# motherboard.net
KiCad netlist of a schematic drawn in EasyEDA Pro
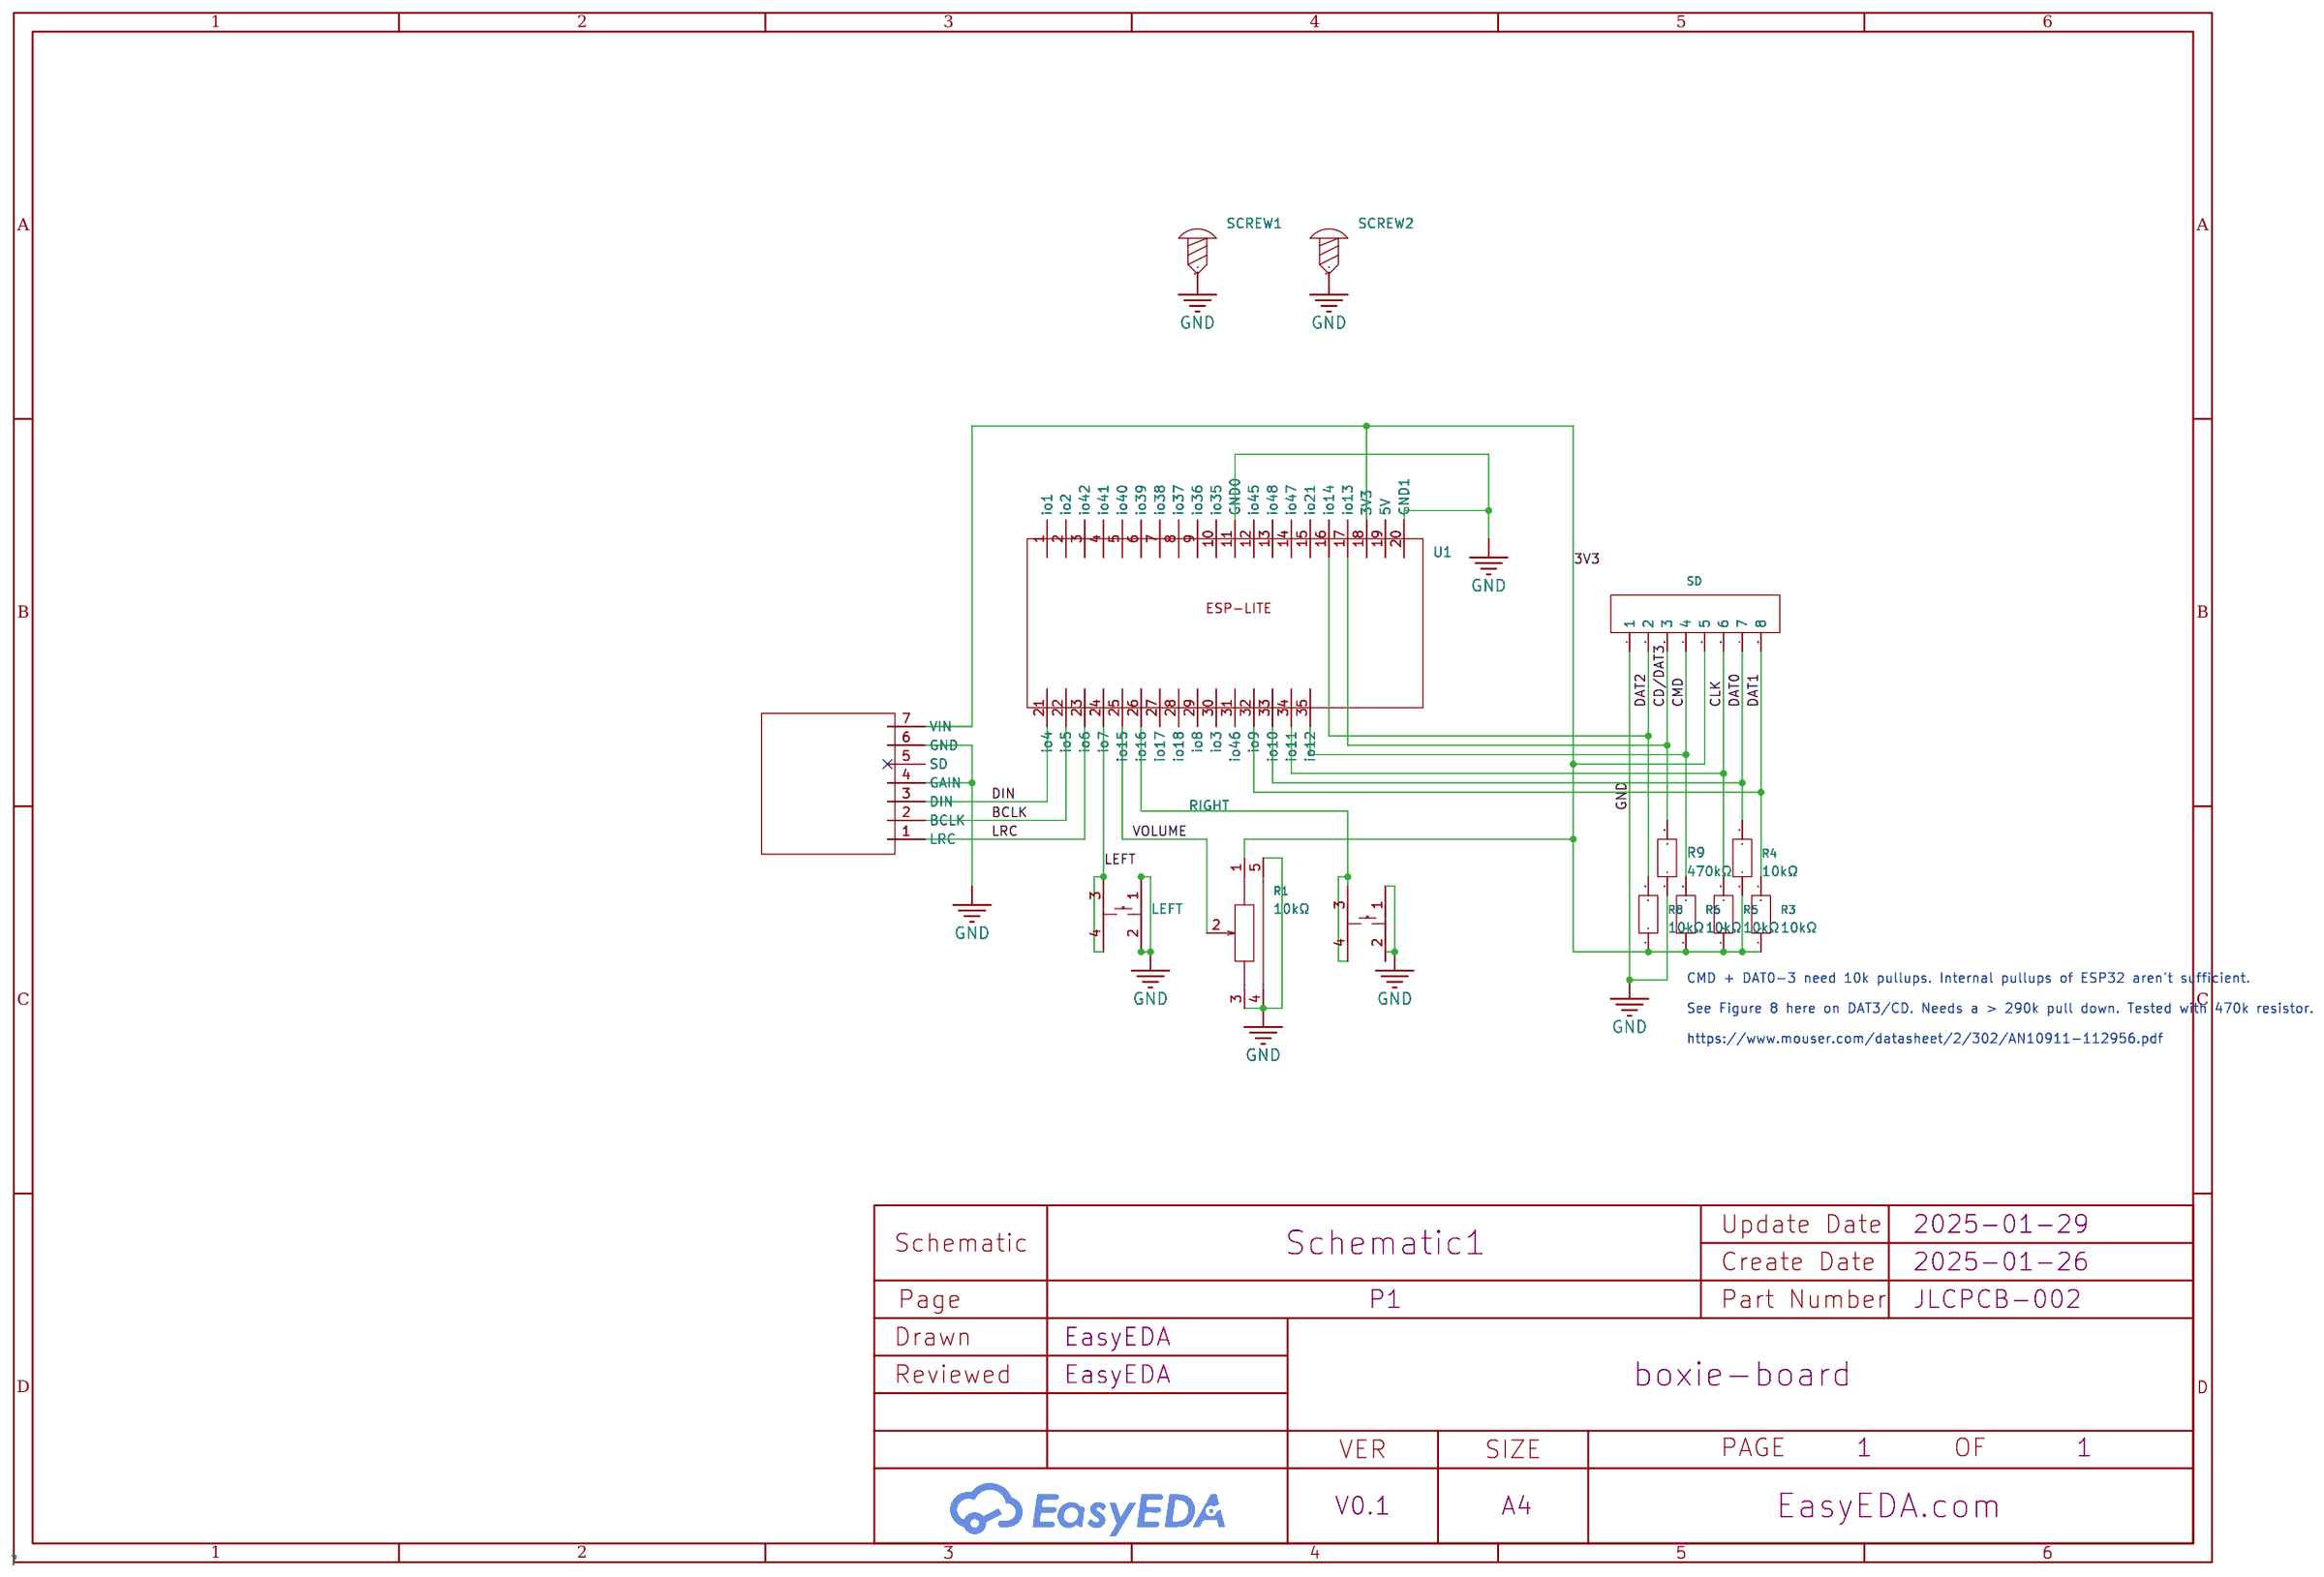
[diagram p0: schematic sheet]

(export (version "E")
  (design (tool "Eeschema 10.0.6"))
  (components
    (comp (ref "LEFT")
      (value "GT-TC074E-H045-L1")
      (footprint "easyedapro:SW-SMD_4P-L4.5-W4.5-P3.00-LS7.5")
      (fields (field (name "Manufacturer") "G-Switch(品赞)"))
      (libsource (lib "easyedapro") (part "GT-TC074E-H045-L1"))
    )
    (comp (ref "R1")
      (value "10kΩ")
      (footprint "easyedapro:RES-TH_RK09K1130AAU")
      (description "Resistance: Tolerance:±20% Tolerance:±20%")
      (fields
        (field (name "Manufacturer Part") "RK09K1130AAU")
        (field (name "Manufacturer") "ALPSALPINE(阿尔卑斯阿尔派)")
      )
      (libsource (lib "easyedapro") (part "RK09K1130AAU"))
    )
    (comp (ref "R3")
      (value "10kΩ")
      (footprint "easyedapro:R0805")
      (fields (field (name "Manufacturer Part") "ERA6VEB1002V") (field (name "Manufacturer") "PANASONIC(松下)"))
      (libsource (lib "easyedapro") (part "ERA6VEB1002V"))
    )
    (comp (ref "R4")
      (value "10kΩ")
      (footprint "easyedapro:R0805")
      (fields (field (name "Manufacturer Part") "ERA6VEB1002V") (field (name "Manufacturer") "PANASONIC(松下)"))
      (libsource (lib "easyedapro") (part "ERA6VEB1002V"))
    )
    (comp (ref "R5")
      (value "10kΩ")
      (footprint "easyedapro:R0805")
      (fields (field (name "Manufacturer Part") "ERA6VEB1002V") (field (name "Manufacturer") "PANASONIC(松下)"))
      (libsource (lib "easyedapro") (part "ERA6VEB1002V"))
    )
    (comp (ref "R6")
      (value "10kΩ")
      (footprint "easyedapro:R0805")
      (fields (field (name "Manufacturer Part") "ERA6VEB1002V") (field (name "Manufacturer") "PANASONIC(松下)"))
      (libsource (lib "easyedapro") (part "ERA6VEB1002V"))
    )
    (comp (ref "R8")
      (value "10kΩ")
      (footprint "easyedapro:R0805")
      (fields (field (name "Manufacturer Part") "ERA6VEB1002V") (field (name "Manufacturer") "PANASONIC(松下)"))
      (libsource (lib "easyedapro") (part "ERA6VEB1002V"))
    )
    (comp (ref "R9")
      (value "470kΩ")
      (footprint "easyedapro:R0805")
      (fields (field (name "Manufacturer Part") "ERJ6GEYJ474V") (field (name "Manufacturer") "PANASONIC(松下)"))
      (libsource (lib "easyedapro") (part "ERJ6GEYJ474V"))
    )
    (comp (ref "RIGHT")
      (value "GT-TC074E-H045-L1")
      (footprint "easyedapro:SW-SMD_4P-L4.5-W4.5-P3.00-LS7.5")
      (fields (field (name "Manufacturer") "G-Switch(品赞)"))
      (libsource (lib "easyedapro") (part "GT-TC074E-H045-L1"))
    )
    (comp (ref "SCREW1")
      (value "~")
      (footprint "easyedapro:Screw-Hole-M3")
      (libsource (lib "easyedapro") (part "Screw-Hole"))
    )
    (comp (ref "SCREW2")
      (value "~")
      (footprint "easyedapro:Screw-Hole-M3")
      (libsource (lib "easyedapro") (part "Screw-Hole"))
    )
    (comp (ref "SD")
      (value "~")
      (footprint "easyedapro:HDR-TH_8P-P2.54-V-F-1")
      (fields (field (name "Manufacturer Part") "2.54-1*8P母环保") (field (name "Manufacturer") "BOOMELE(博穆精密)"))
      (libsource (lib "easyedapro") (part "Header-Female-2.54_1x8"))
    )
    (comp (ref "U1")
      (value "~")
      (footprint "easyedapro:esp32-lite")
      (libsource (lib "easyedapro") (part "esp32-lite"))
    )
    (comp (ref "U4")
      (value "MAX98357A-I2S")
      (footprint "easyedapro:MAX98357A_I2S_footprint")
      (libsource (lib "easyedapro") (part "MAX98357 Breakboard"))
    )
  )
  (nets
    (net (code "1") (name "/3V3") (class "Default")
      (node (ref "R1") (pin "1") (pinfunction "1_1") (pintype "input"))
      (node (ref "R3") (pin "1") (pinfunction "1_1") (pintype "input"))
      (node (ref "R4") (pin "2") (pinfunction "2_2") (pintype "input"))
      (node (ref "R5") (pin "1") (pinfunction "1_1") (pintype "input"))
      (node (ref "R6") (pin "1") (pinfunction "1_1") (pintype "input"))
      (node (ref "R8") (pin "1") (pinfunction "1_1") (pintype "input"))
      (node (ref "SD") (pin "5") (pinfunction "5_5") (pintype "input"))
      (node (ref "U1") (pin "18") (pinfunction "3V3_18") (pintype "bidirectional"))
      (node (ref "U4") (pin "7") (pinfunction "VIN_7") (pintype "unspecified"))
    )
    (net (code "2") (name "/BCLK") (class "Default")
      (node (ref "U1") (pin "22") (pinfunction "io5_22") (pintype "bidirectional"))
      (node (ref "U4") (pin "2") (pinfunction "BCLK_2") (pintype "unspecified"))
    )
    (net (code "3") (name "/CD{slash}DAT3") (class "Default")
      (node (ref "R9") (pin "2") (pinfunction "2_2") (pintype "unspecified"))
      (node (ref "SD") (pin "3") (pinfunction "3_3") (pintype "input"))
      (node (ref "U1") (pin "17") (pinfunction "io13_17") (pintype "bidirectional"))
    )
    (net (code "4") (name "/CLK") (class "Default")
      (node (ref "R5") (pin "2") (pinfunction "2_2") (pintype "input"))
      (node (ref "SD") (pin "6") (pinfunction "6_6") (pintype "input"))
      (node (ref "U1") (pin "34") (pinfunction "io11_34") (pintype "bidirectional"))
    )
    (net (code "5") (name "/CMD") (class "Default")
      (node (ref "R6") (pin "2") (pinfunction "2_2") (pintype "input"))
      (node (ref "SD") (pin "4") (pinfunction "4_4") (pintype "input"))
      (node (ref "U1") (pin "35") (pinfunction "io12_35") (pintype "bidirectional"))
    )
    (net (code "6") (name "/DAT0") (class "Default")
      (node (ref "R4") (pin "1") (pinfunction "1_1") (pintype "input"))
      (node (ref "SD") (pin "7") (pinfunction "7_7") (pintype "input"))
      (node (ref "U1") (pin "33") (pinfunction "io10_33") (pintype "bidirectional"))
    )
    (net (code "7") (name "/DAT1") (class "Default")
      (node (ref "R3") (pin "2") (pinfunction "2_2") (pintype "input"))
      (node (ref "SD") (pin "8") (pinfunction "8_8") (pintype "input"))
      (node (ref "U1") (pin "32") (pinfunction "io9_32") (pintype "bidirectional"))
    )
    (net (code "8") (name "/DAT2") (class "Default")
      (node (ref "R8") (pin "2") (pinfunction "2_2") (pintype "input"))
      (node (ref "SD") (pin "2") (pinfunction "2_2") (pintype "input"))
      (node (ref "U1") (pin "16") (pinfunction "io14_16") (pintype "bidirectional"))
    )
    (net (code "9") (name "/DIN") (class "Default")
      (node (ref "U1") (pin "21") (pinfunction "io4_21") (pintype "bidirectional"))
      (node (ref "U4") (pin "3") (pinfunction "DIN_3") (pintype "unspecified"))
    )
    (net (code "10") (name "/LEFT") (class "Default")
      (node (ref "LEFT") (pin "3") (pinfunction "3_3") (pintype "unspecified"))
      (node (ref "LEFT") (pin "4") (pinfunction "4_4") (pintype "unspecified"))
      (node (ref "U1") (pin "24") (pinfunction "io7_24") (pintype "bidirectional"))
    )
    (net (code "11") (name "/LRC") (class "Default")
      (node (ref "U1") (pin "23") (pinfunction "io6_23") (pintype "bidirectional"))
      (node (ref "U4") (pin "1") (pinfunction "LRC_1") (pintype "unspecified"))
    )
    (net (code "12") (name "/VOLUME") (class "Default")
      (node (ref "R1") (pin "2") (pinfunction "2_2") (pintype "input"))
      (node (ref "U1") (pin "25") (pinfunction "io15_25") (pintype "bidirectional"))
    )
    (net (code "13") (name "GND") (class "Default")
      (node (ref "LEFT") (pin "1") (pinfunction "1_1") (pintype "unspecified"))
      (node (ref "LEFT") (pin "2") (pinfunction "2_2") (pintype "unspecified"))
      (node (ref "R1") (pin "3") (pinfunction "3_3") (pintype "input"))
      (node (ref "R1") (pin "4") (pinfunction "EH_4") (pintype "input"))
      (node (ref "R1") (pin "5") (pinfunction "EH_5") (pintype "input"))
      (node (ref "R9") (pin "1") (pinfunction "1_1") (pintype "unspecified"))
      (node (ref "RIGHT") (pin "1") (pinfunction "1_1") (pintype "unspecified"))
      (node (ref "RIGHT") (pin "2") (pinfunction "2_2") (pintype "unspecified"))
      (node (ref "SCREW1") (pin "1") (pinfunction "1_1") (pintype "input"))
      (node (ref "SCREW2") (pin "1") (pinfunction "1_1") (pintype "input"))
      (node (ref "SD") (pin "1") (pinfunction "1_1") (pintype "input"))
      (node (ref "U1") (pin "11") (pinfunction "GND0_11") (pintype "bidirectional"))
      (node (ref "U1") (pin "20") (pinfunction "GND1_20") (pintype "bidirectional"))
      (node (ref "U4") (pin "4") (pinfunction "GAIN_4") (pintype "unspecified"))
      (node (ref "U4") (pin "6") (pinfunction "GND_6") (pintype "unspecified"))
    )
    (net (code "14") (name "Net-(U1-io16)") (class "Default")
      (node (ref "RIGHT") (pin "3") (pinfunction "3_3") (pintype "unspecified"))
      (node (ref "RIGHT") (pin "4") (pinfunction "4_4") (pintype "unspecified"))
      (node (ref "U1") (pin "26") (pinfunction "io16_26") (pintype "bidirectional"))
    )
    (net (code "15") (name "unconnected-(U1-5V-Pad19)") (class "Default")
      (node (ref "U1") (pin "19") (pinfunction "5V_19") (pintype "input"))
    )
    (net (code "16") (name "unconnected-(U1-io1-Pad1)") (class "Default")
      (node (ref "U1") (pin "1") (pinfunction "io1_1") (pintype "bidirectional"))
    )
    (net (code "17") (name "unconnected-(U1-io2-Pad2)") (class "Default")
      (node (ref "U1") (pin "2") (pinfunction "io2_2") (pintype "bidirectional"))
    )
    (net (code "18") (name "unconnected-(U1-io3-Pad30)") (class "Default")
      (node (ref "U1") (pin "30") (pinfunction "io3_30") (pintype "bidirectional"))
    )
    (net (code "19") (name "unconnected-(U1-io8-Pad29)") (class "Default")
      (node (ref "U1") (pin "29") (pinfunction "io8_29") (pintype "bidirectional"))
    )
    (net (code "20") (name "unconnected-(U1-io17-Pad27)") (class "Default")
      (node (ref "U1") (pin "27") (pinfunction "io17_27") (pintype "bidirectional"))
    )
    (net (code "21") (name "unconnected-(U1-io18-Pad28)") (class "Default")
      (node (ref "U1") (pin "28") (pinfunction "io18_28") (pintype "bidirectional"))
    )
    (net (code "22") (name "unconnected-(U1-io21-Pad15)") (class "Default")
      (node (ref "U1") (pin "15") (pinfunction "io21_15") (pintype "bidirectional"))
    )
    (net (code "23") (name "unconnected-(U1-io35-Pad10)") (class "Default")
      (node (ref "U1") (pin "10") (pinfunction "io35_10") (pintype "bidirectional"))
    )
    (net (code "24") (name "unconnected-(U1-io36-Pad9)") (class "Default")
      (node (ref "U1") (pin "9") (pinfunction "io36_9") (pintype "bidirectional"))
    )
    (net (code "25") (name "unconnected-(U1-io37-Pad8)") (class "Default")
      (node (ref "U1") (pin "8") (pinfunction "io37_8") (pintype "bidirectional"))
    )
    (net (code "26") (name "unconnected-(U1-io38-Pad7)") (class "Default")
      (node (ref "U1") (pin "7") (pinfunction "io38_7") (pintype "bidirectional"))
    )
    (net (code "27") (name "unconnected-(U1-io39-Pad6)") (class "Default")
      (node (ref "U1") (pin "6") (pinfunction "io39_6") (pintype "bidirectional"))
    )
    (net (code "28") (name "unconnected-(U1-io40-Pad5)") (class "Default")
      (node (ref "U1") (pin "5") (pinfunction "io40_5") (pintype "bidirectional"))
    )
    (net (code "29") (name "unconnected-(U1-io41-Pad4)") (class "Default")
      (node (ref "U1") (pin "4") (pinfunction "io41_4") (pintype "bidirectional"))
    )
    (net (code "30") (name "unconnected-(U1-io42-Pad3)") (class "Default")
      (node (ref "U1") (pin "3") (pinfunction "io42_3") (pintype "bidirectional"))
    )
    (net (code "31") (name "unconnected-(U1-io45-Pad12)") (class "Default")
      (node (ref "U1") (pin "12") (pinfunction "io45_12") (pintype "bidirectional"))
    )
    (net (code "32") (name "unconnected-(U1-io46-Pad31)") (class "Default")
      (node (ref "U1") (pin "31") (pinfunction "io46_31") (pintype "bidirectional"))
    )
    (net (code "33") (name "unconnected-(U1-io47-Pad14)") (class "Default")
      (node (ref "U1") (pin "14") (pinfunction "io47_14") (pintype "bidirectional"))
    )
    (net (code "34") (name "unconnected-(U1-io48-Pad13)") (class "Default")
      (node (ref "U1") (pin "13") (pinfunction "io48_13") (pintype "bidirectional"))
    )
    (net (code "35") (name "unconnected-(U4-SD-Pad5)") (class "Default")
      (node (ref "U4") (pin "5") (pinfunction "SD_5") (pintype "unspecified+no_connect"))
    )
  )
)
